# Teensy_PCB_Schematic.net
KiCad netlist of a schematic drawn in Altium Designer
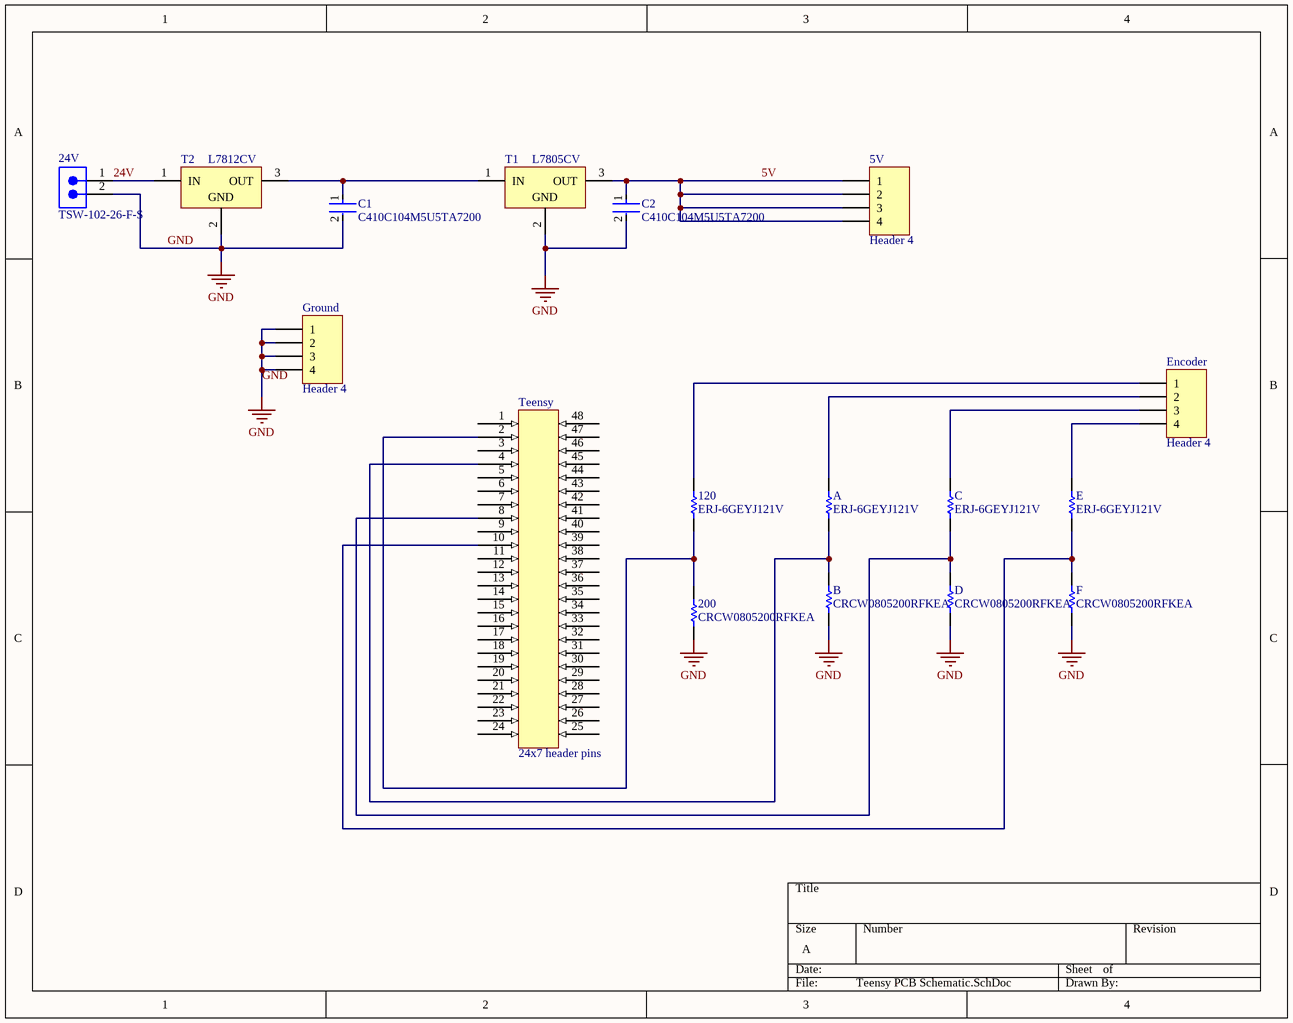
[diagram p0: Teensy PCB Schematic.SchDoc]

(export (version "E")
  (design (tool "Eeschema 10.0.6"))
  (components
    (comp (ref "5V")
      (value "Header 4")
      (footprint "HDR1X4")
      (description "Header, 4-Pin")
      (fields (field (name "PUBLISHER") "Altium Limited"))
      (libsource (lib "Gopher Motorsports") (part "Symbol"))
    )
    (comp (ref "24V")
      (value "TSW-102-26-F-S")
      (footprint "SMTC-TSW-102-26-XX-S")
      (description "0.025\" SQ Post Header, Through-hole, Vertical, -55 to 125 degC, 2.54 mm Pitch, 2-Pin, Male, RoHS")
      (fields (field (name "MANUFACTURER") "Samtec"))
      (libsource (lib "Altium Content Vault") (part "SMTC-TSW-102-X-X-S-X"))
    )
    (comp (ref "120")
      (value "ERJ-6GEYJ121V")
      (footprint "RESC2013X70X40LL20T20")
      (fields (field (name "MANUFACTURER") "Panasonic"))
      (libsource (lib "Altium Content Vault") (part "RES"))
    )
    (comp (ref "200")
      (value "CRCW0805200RFKEA")
      (footprint "RESC2013X50X30NL20T20")
      (fields (field (name "MANUFACTURER") "Vishay Dale"))
      (libsource (lib "Altium Content Vault") (part "RES"))
    )
    (comp (ref "A")
      (value "ERJ-6GEYJ121V")
      (footprint "RESC2013X70X40LL20T20")
      (fields (field (name "MANUFACTURER") "Panasonic"))
      (libsource (lib "Altium Content Vault") (part "RES"))
    )
    (comp (ref "B")
      (value "CRCW0805200RFKEA")
      (footprint "RESC2013X50X30NL20T20")
      (fields (field (name "MANUFACTURER") "Vishay Dale"))
      (libsource (lib "Altium Content Vault") (part "RES"))
    )
    (comp (ref "C")
      (value "ERJ-6GEYJ121V")
      (footprint "RESC2013X70X40LL20T20")
      (fields (field (name "MANUFACTURER") "Panasonic"))
      (libsource (lib "Altium Content Vault") (part "RES"))
    )
    (comp (ref "C1")
      (value "C410C104M5U5TA7200")
      (footprint "FP-C410C104M5U5TA7200-MFG")
      (description "CAP CER 0.1UF 50V Z5U AXIAL")
      (fields (field (name "TOLERANCE") "20%"))
      (libsource (lib "Altium Content Vault") (part "b4654b650e69147ec39a6b967a45e02"))
    )
    (comp (ref "C2")
      (value "C410C104M5U5TA7200")
      (footprint "FP-C410C104M5U5TA7200-MFG")
      (description "CAP CER 0.1UF 50V Z5U AXIAL")
      (fields (field (name "TOLERANCE") "20%"))
      (libsource (lib "Altium Content Vault") (part "b4654b650e69147ec39a6b967a45e02"))
    )
    (comp (ref "D")
      (value "CRCW0805200RFKEA")
      (footprint "RESC2013X50X30NL20T20")
      (fields (field (name "MANUFACTURER") "Vishay Dale"))
      (libsource (lib "Altium Content Vault") (part "RES"))
    )
    (comp (ref "E")
      (value "ERJ-6GEYJ121V")
      (footprint "RESC2013X70X40LL20T20")
      (fields (field (name "MANUFACTURER") "Panasonic"))
      (libsource (lib "Altium Content Vault") (part "RES"))
    )
    (comp (ref "Encoder")
      (value "Header 4")
      (footprint "HDR1X4")
      (description "Header, 4-Pin")
      (fields (field (name "PUBLISHER") "Altium Limited"))
      (libsource (lib "Gopher Motorsports") (part "Symbol"))
    )
    (comp (ref "F")
      (value "CRCW0805200RFKEA")
      (footprint "RESC2013X50X30NL20T20")
      (fields (field (name "MANUFACTURER") "Vishay Dale"))
      (libsource (lib "Altium Content Vault") (part "RES"))
    )
    (comp (ref "Ground")
      (value "Header 4")
      (footprint "HDR1X4")
      (description "Header, 4-Pin")
      (fields (field (name "PUBLISHER") "Altium Limited"))
      (libsource (lib "Gopher Motorsports") (part "Symbol"))
    )
    (comp (ref "T1")
      (value "L7805CV")
      (footprint "TO220")
      (description "Positive Voltage Regulator, 5V, 3-Pin TO-220")
      (libsource (lib "Altium Content Vault") (part "PM-REG-L4940-SIL3"))
    )
    (comp (ref "T2")
      (value "L7812CV")
      (footprint "TO220")
      (description "Positive Voltage Regulator, 12V, 3-Pin TO-220")
      (libsource (lib "Altium Content Vault") (part "PM-REG-L4940-SIL3"))
    )
    (comp (ref "Teensy")
      (value "24x7 header pins")
      (footprint "New footprint 1")
      (description "for teensy 3.6")
      (libsource (lib "Gopher Motorsports") (part "New symbol 1"))
    )
  )
  (nets
    (net (code "1") (name "/5V") (class "Default")
      (node (ref "5V") (pin "1") (pinfunction "1_1") (pintype "passive"))
      (node (ref "5V") (pin "2") (pinfunction "2_2") (pintype "passive"))
      (node (ref "5V") (pin "3") (pinfunction "3_3") (pintype "passive"))
      (node (ref "5V") (pin "4") (pinfunction "4_4") (pintype "passive"))
      (node (ref "C2") (pin "1") (pinfunction "1_1") (pintype "passive"))
      (node (ref "T1") (pin "3") (pinfunction "OUT_3") (pintype "power_in"))
    )
    (net (code "2") (name "/24V") (class "Default")
      (node (ref "24V") (pin "1") (pinfunction "1_1") (pintype "passive"))
      (node (ref "T2") (pin "1") (pinfunction "IN_1") (pintype "power_in"))
    )
    (net (code "3") (name "GND") (class "Default")
      (node (ref "200") (pin "1") (pinfunction "1_1") (pintype "passive"))
      (node (ref "24V") (pin "2") (pinfunction "2_2") (pintype "passive"))
      (node (ref "B") (pin "1") (pinfunction "1_1") (pintype "passive"))
      (node (ref "C1") (pin "2") (pinfunction "2_2") (pintype "passive"))
      (node (ref "C2") (pin "2") (pinfunction "2_2") (pintype "passive"))
      (node (ref "D") (pin "1") (pinfunction "1_1") (pintype "passive"))
      (node (ref "F") (pin "1") (pinfunction "1_1") (pintype "passive"))
      (node (ref "Ground") (pin "1") (pinfunction "1_1") (pintype "passive"))
      (node (ref "Ground") (pin "2") (pinfunction "2_2") (pintype "passive"))
      (node (ref "Ground") (pin "3") (pinfunction "3_3") (pintype "passive"))
      (node (ref "Ground") (pin "4") (pinfunction "4_4") (pintype "passive"))
      (node (ref "T1") (pin "2") (pinfunction "GND_2") (pintype "power_in"))
      (node (ref "T2") (pin "2") (pinfunction "GND_2") (pintype "power_in"))
    )
    (net (code "4") (name "Net-(120-Pad1)") (class "Default")
      (node (ref "120") (pin "1") (pinfunction "1_1") (pintype "passive"))
      (node (ref "200") (pin "2") (pinfunction "2_2") (pintype "passive"))
      (node (ref "Teensy") (pin "2") (pintype "input"))
    )
    (net (code "5") (name "Net-(120-Pad2)") (class "Default")
      (node (ref "120") (pin "2") (pinfunction "2_2") (pintype "passive"))
      (node (ref "Encoder") (pin "1") (pinfunction "1_1") (pintype "passive"))
    )
    (net (code "6") (name "Net-(A-Pad1)") (class "Default")
      (node (ref "A") (pin "1") (pinfunction "1_1") (pintype "passive"))
      (node (ref "B") (pin "2") (pinfunction "2_2") (pintype "passive"))
      (node (ref "Teensy") (pin "4") (pintype "input"))
    )
    (net (code "7") (name "Net-(A-Pad2)") (class "Default")
      (node (ref "A") (pin "2") (pinfunction "2_2") (pintype "passive"))
      (node (ref "Encoder") (pin "2") (pinfunction "2_2") (pintype "passive"))
    )
    (net (code "8") (name "Net-(C-Pad1)") (class "Default")
      (node (ref "C") (pin "1") (pinfunction "1_1") (pintype "passive"))
      (node (ref "D") (pin "2") (pinfunction "2_2") (pintype "passive"))
      (node (ref "Teensy") (pin "8") (pintype "input"))
    )
    (net (code "9") (name "Net-(C-Pad2)") (class "Default")
      (node (ref "C") (pin "2") (pinfunction "2_2") (pintype "passive"))
      (node (ref "Encoder") (pin "3") (pinfunction "3_3") (pintype "passive"))
    )
    (net (code "10") (name "Net-(E-Pad1)") (class "Default")
      (node (ref "E") (pin "1") (pinfunction "1_1") (pintype "passive"))
      (node (ref "F") (pin "2") (pinfunction "2_2") (pintype "passive"))
      (node (ref "Teensy") (pin "10") (pintype "input"))
    )
    (net (code "11") (name "Net-(E-Pad2)") (class "Default")
      (node (ref "E") (pin "2") (pinfunction "2_2") (pintype "passive"))
      (node (ref "Encoder") (pin "4") (pinfunction "4_4") (pintype "passive"))
    )
    (net (code "12") (name "Net-(T1-IN)") (class "Default")
      (node (ref "C1") (pin "1") (pinfunction "1_1") (pintype "passive"))
      (node (ref "T1") (pin "1") (pinfunction "IN_1") (pintype "power_in"))
      (node (ref "T2") (pin "3") (pinfunction "OUT_3") (pintype "power_in"))
    )
    (net (code "13") (name "unconnected-(Teensy-Pad1)") (class "Default")
      (node (ref "Teensy") (pin "1") (pintype "input"))
    )
    (net (code "14") (name "unconnected-(Teensy-Pad3)") (class "Default")
      (node (ref "Teensy") (pin "3") (pintype "input"))
    )
    (net (code "15") (name "unconnected-(Teensy-Pad5)") (class "Default")
      (node (ref "Teensy") (pin "5") (pintype "input"))
    )
    (net (code "16") (name "unconnected-(Teensy-Pad6)") (class "Default")
      (node (ref "Teensy") (pin "6") (pintype "input"))
    )
    (net (code "17") (name "unconnected-(Teensy-Pad7)") (class "Default")
      (node (ref "Teensy") (pin "7") (pintype "input"))
    )
    (net (code "18") (name "unconnected-(Teensy-Pad9)") (class "Default")
      (node (ref "Teensy") (pin "9") (pintype "input"))
    )
    (net (code "19") (name "unconnected-(Teensy-Pad11)") (class "Default")
      (node (ref "Teensy") (pin "11") (pintype "input"))
    )
    (net (code "20") (name "unconnected-(Teensy-Pad12)") (class "Default")
      (node (ref "Teensy") (pin "12") (pintype "input"))
    )
    (net (code "21") (name "unconnected-(Teensy-Pad13)") (class "Default")
      (node (ref "Teensy") (pin "13") (pintype "input"))
    )
    (net (code "22") (name "unconnected-(Teensy-Pad14)") (class "Default")
      (node (ref "Teensy") (pin "14") (pintype "input"))
    )
    (net (code "23") (name "unconnected-(Teensy-Pad15)") (class "Default")
      (node (ref "Teensy") (pin "15") (pintype "input"))
    )
    (net (code "24") (name "unconnected-(Teensy-Pad16)") (class "Default")
      (node (ref "Teensy") (pin "16") (pintype "input"))
    )
    (net (code "25") (name "unconnected-(Teensy-Pad17)") (class "Default")
      (node (ref "Teensy") (pin "17") (pintype "input"))
    )
    (net (code "26") (name "unconnected-(Teensy-Pad18)") (class "Default")
      (node (ref "Teensy") (pin "18") (pintype "input"))
    )
    (net (code "27") (name "unconnected-(Teensy-Pad19)") (class "Default")
      (node (ref "Teensy") (pin "19") (pintype "input"))
    )
    (net (code "28") (name "unconnected-(Teensy-Pad20)") (class "Default")
      (node (ref "Teensy") (pin "20") (pintype "input"))
    )
    (net (code "29") (name "unconnected-(Teensy-Pad21)") (class "Default")
      (node (ref "Teensy") (pin "21") (pintype "input"))
    )
    (net (code "30") (name "unconnected-(Teensy-Pad22)") (class "Default")
      (node (ref "Teensy") (pin "22") (pintype "input"))
    )
    (net (code "31") (name "unconnected-(Teensy-Pad23)") (class "Default")
      (node (ref "Teensy") (pin "23") (pintype "input"))
    )
    (net (code "32") (name "unconnected-(Teensy-Pad24)") (class "Default")
      (node (ref "Teensy") (pin "24") (pintype "input"))
    )
    (net (code "33") (name "unconnected-(Teensy-Pad25)") (class "Default")
      (node (ref "Teensy") (pin "25") (pintype "input"))
    )
    (net (code "34") (name "unconnected-(Teensy-Pad26)") (class "Default")
      (node (ref "Teensy") (pin "26") (pintype "input"))
    )
    (net (code "35") (name "unconnected-(Teensy-Pad27)") (class "Default")
      (node (ref "Teensy") (pin "27") (pintype "input"))
    )
    (net (code "36") (name "unconnected-(Teensy-Pad28)") (class "Default")
      (node (ref "Teensy") (pin "28") (pintype "input"))
    )
    (net (code "37") (name "unconnected-(Teensy-Pad29)") (class "Default")
      (node (ref "Teensy") (pin "29") (pintype "input"))
    )
    (net (code "38") (name "unconnected-(Teensy-Pad30)") (class "Default")
      (node (ref "Teensy") (pin "30") (pintype "input"))
    )
    (net (code "39") (name "unconnected-(Teensy-Pad31)") (class "Default")
      (node (ref "Teensy") (pin "31") (pintype "input"))
    )
    (net (code "40") (name "unconnected-(Teensy-Pad32)") (class "Default")
      (node (ref "Teensy") (pin "32") (pintype "input"))
    )
    (net (code "41") (name "unconnected-(Teensy-Pad33)") (class "Default")
      (node (ref "Teensy") (pin "33") (pintype "input"))
    )
    (net (code "42") (name "unconnected-(Teensy-Pad34)") (class "Default")
      (node (ref "Teensy") (pin "34") (pintype "input"))
    )
    (net (code "43") (name "unconnected-(Teensy-Pad35)") (class "Default")
      (node (ref "Teensy") (pin "35") (pintype "input"))
    )
    (net (code "44") (name "unconnected-(Teensy-Pad36)") (class "Default")
      (node (ref "Teensy") (pin "36") (pintype "input"))
    )
    (net (code "45") (name "unconnected-(Teensy-Pad37)") (class "Default")
      (node (ref "Teensy") (pin "37") (pintype "input"))
    )
    (net (code "46") (name "unconnected-(Teensy-Pad38)") (class "Default")
      (node (ref "Teensy") (pin "38") (pintype "input"))
    )
    (net (code "47") (name "unconnected-(Teensy-Pad39)") (class "Default")
      (node (ref "Teensy") (pin "39") (pintype "input"))
    )
    (net (code "48") (name "unconnected-(Teensy-Pad40)") (class "Default")
      (node (ref "Teensy") (pin "40") (pintype "input"))
    )
    (net (code "49") (name "unconnected-(Teensy-Pad41)") (class "Default")
      (node (ref "Teensy") (pin "41") (pintype "input"))
    )
    (net (code "50") (name "unconnected-(Teensy-Pad42)") (class "Default")
      (node (ref "Teensy") (pin "42") (pintype "input"))
    )
    (net (code "51") (name "unconnected-(Teensy-Pad43)") (class "Default")
      (node (ref "Teensy") (pin "43") (pintype "input"))
    )
    (net (code "52") (name "unconnected-(Teensy-Pad44)") (class "Default")
      (node (ref "Teensy") (pin "44") (pintype "input"))
    )
    (net (code "53") (name "unconnected-(Teensy-Pad45)") (class "Default")
      (node (ref "Teensy") (pin "45") (pintype "input"))
    )
    (net (code "54") (name "unconnected-(Teensy-Pad46)") (class "Default")
      (node (ref "Teensy") (pin "46") (pintype "input"))
    )
    (net (code "55") (name "unconnected-(Teensy-Pad47)") (class "Default")
      (node (ref "Teensy") (pin "47") (pintype "input"))
    )
    (net (code "56") (name "unconnected-(Teensy-Pad48)") (class "Default")
      (node (ref "Teensy") (pin "48") (pintype "input"))
    )
  )
)
